# LTC6803-3.net
KiCad netlist of a schematic drawn in Altium Designer
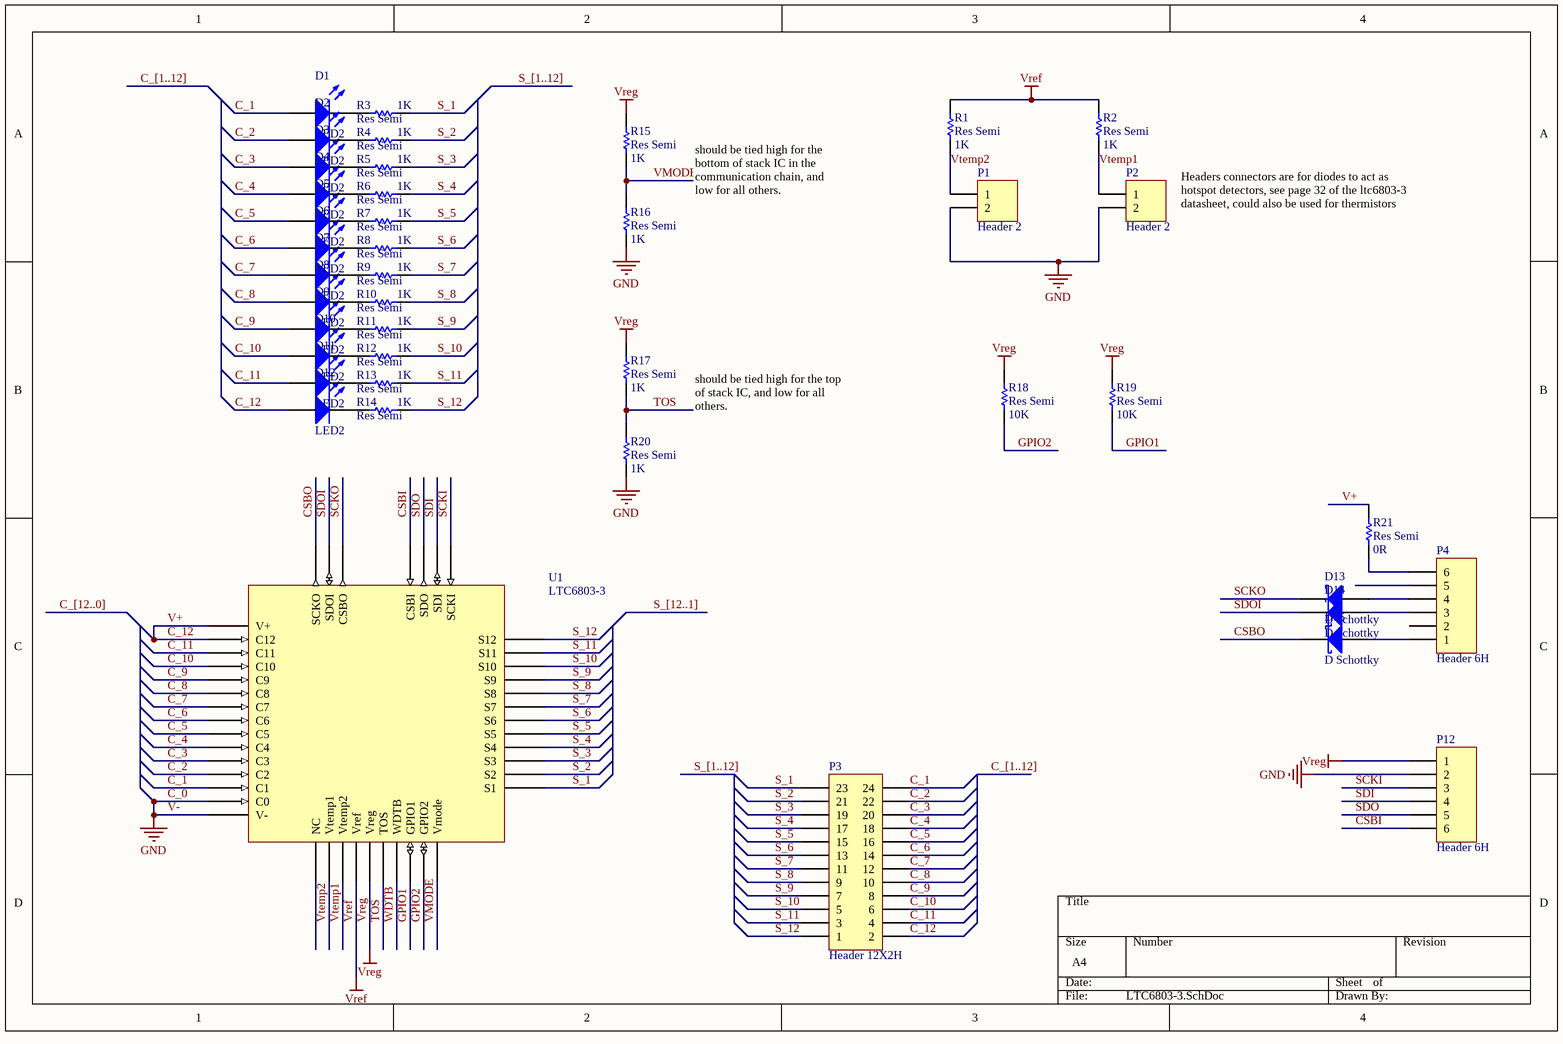
[diagram p0: LTC6803-3.SchDoc]

(export (version "E")
  (design (tool "Eeschema 10.0.6"))
  (components
    (comp (ref "D1")
      (value "LED2")
      (footprint "6-0805_N")
      (description "Typical RED, GREEN, YELLOW, AMBER GaAs LED")
      (fields (field (name "PUBLISHER") "Altium Limited"))
      (libsource (lib "Miscellaneous Devices") (part "LED2"))
    )
    (comp (ref "D2")
      (value "LED2")
      (footprint "6-0805_N")
      (description "Typical RED, GREEN, YELLOW, AMBER GaAs LED")
      (fields (field (name "PUBLISHER") "Altium Limited"))
      (libsource (lib "Miscellaneous Devices") (part "LED2"))
    )
    (comp (ref "D3")
      (value "LED2")
      (footprint "6-0805_N")
      (description "Typical RED, GREEN, YELLOW, AMBER GaAs LED")
      (fields (field (name "PUBLISHER") "Altium Limited"))
      (libsource (lib "Miscellaneous Devices") (part "LED2"))
    )
    (comp (ref "D4")
      (value "LED2")
      (footprint "6-0805_N")
      (description "Typical RED, GREEN, YELLOW, AMBER GaAs LED")
      (fields (field (name "PUBLISHER") "Altium Limited"))
      (libsource (lib "Miscellaneous Devices") (part "LED2"))
    )
    (comp (ref "D5")
      (value "LED2")
      (footprint "6-0805_N")
      (description "Typical RED, GREEN, YELLOW, AMBER GaAs LED")
      (fields (field (name "PUBLISHER") "Altium Limited"))
      (libsource (lib "Miscellaneous Devices") (part "LED2"))
    )
    (comp (ref "D6")
      (value "LED2")
      (footprint "6-0805_N")
      (description "Typical RED, GREEN, YELLOW, AMBER GaAs LED")
      (fields (field (name "PUBLISHER") "Altium Limited"))
      (libsource (lib "Miscellaneous Devices") (part "LED2"))
    )
    (comp (ref "D7")
      (value "LED2")
      (footprint "6-0805_N")
      (description "Typical RED, GREEN, YELLOW, AMBER GaAs LED")
      (fields (field (name "PUBLISHER") "Altium Limited"))
      (libsource (lib "Miscellaneous Devices") (part "LED2"))
    )
    (comp (ref "D8")
      (value "LED2")
      (footprint "6-0805_N")
      (description "Typical RED, GREEN, YELLOW, AMBER GaAs LED")
      (fields (field (name "PUBLISHER") "Altium Limited"))
      (libsource (lib "Miscellaneous Devices") (part "LED2"))
    )
    (comp (ref "D9")
      (value "LED2")
      (footprint "6-0805_N")
      (description "Typical RED, GREEN, YELLOW, AMBER GaAs LED")
      (fields (field (name "PUBLISHER") "Altium Limited"))
      (libsource (lib "Miscellaneous Devices") (part "LED2"))
    )
    (comp (ref "D10")
      (value "LED2")
      (footprint "6-0805_N")
      (description "Typical RED, GREEN, YELLOW, AMBER GaAs LED")
      (fields (field (name "PUBLISHER") "Altium Limited"))
      (libsource (lib "Miscellaneous Devices") (part "LED2"))
    )
    (comp (ref "D11")
      (value "LED2")
      (footprint "6-0805_N")
      (description "Typical RED, GREEN, YELLOW, AMBER GaAs LED")
      (fields (field (name "PUBLISHER") "Altium Limited"))
      (libsource (lib "Miscellaneous Devices") (part "LED2"))
    )
    (comp (ref "D12")
      (value "LED2")
      (footprint "6-0805_N")
      (description "Typical RED, GREEN, YELLOW, AMBER GaAs LED")
      (fields (field (name "PUBLISHER") "Altium Limited"))
      (libsource (lib "Miscellaneous Devices") (part "LED2"))
    )
    (comp (ref "D13")
      (value "D Schottky")
      (footprint "SMB")
      (description "Schottky Diode")
      (fields (field (name "PUBLISHER") "Altium Limited"))
      (libsource (lib "Miscellaneous Devices") (part "D Schottky"))
    )
    (comp (ref "D14")
      (value "D Schottky")
      (footprint "SMB")
      (description "Schottky Diode")
      (fields (field (name "PUBLISHER") "Altium Limited"))
      (libsource (lib "Miscellaneous Devices") (part "D Schottky"))
    )
    (comp (ref "D15")
      (value "D Schottky")
      (footprint "SMB")
      (description "Schottky Diode")
      (fields (field (name "PUBLISHER") "Altium Limited"))
      (libsource (lib "Miscellaneous Devices") (part "D Schottky"))
    )
    (comp (ref "P1")
      (value "Header 2")
      (footprint "HDR1X2")
      (description "Header, 2-Pin")
      (fields (field (name "PUBLISHER") "Altium Limited"))
      (libsource (lib "Miscellaneous Connectors") (part "Header 2"))
    )
    (comp (ref "P2")
      (value "Header 2")
      (footprint "HDR1X2")
      (description "Header, 2-Pin")
      (fields (field (name "PUBLISHER") "Altium Limited"))
      (libsource (lib "Miscellaneous Connectors") (part "Header 2"))
    )
    (comp (ref "P3")
      (value "Header 12X2H")
      (footprint "HDR2X12H")
      (description "Header, 12-Pin, Dual row, Right Angle")
      (fields (field (name "PUBLISHER") "Altium Limited"))
      (libsource (lib "Miscellaneous Connectors") (part "Header 12X2H"))
    )
    (comp (ref "P4")
      (value "Header 6H")
      (footprint "HDR1X6H")
      (description "Header, 6-Pin, Right Angle")
      (fields (field (name "PUBLISHER") "Altium Limited"))
      (libsource (lib "") (part "Header 6H_1"))
    )
    (comp (ref "P12")
      (value "Header 6H")
      (footprint "HDR1X6H")
      (description "Header, 6-Pin, Right Angle")
      (fields (field (name "PUBLISHER") "Altium Limited"))
      (libsource (lib "Miscellaneous Connectors") (part "Header 6H"))
    )
    (comp (ref "R1")
      (value "Res Semi")
      (footprint "6-0805_L")
      (description "Semiconductor Resistor")
      (fields (field (name "ALTIUM_VALUE") "1K") (field (name "PUBLISHER") "Altium Limited"))
      (libsource (lib "Miscellaneous Devices") (part "Res Semi"))
    )
    (comp (ref "R2")
      (value "Res Semi")
      (footprint "6-0805_L")
      (description "Semiconductor Resistor")
      (fields (field (name "ALTIUM_VALUE") "1K") (field (name "PUBLISHER") "Altium Limited"))
      (libsource (lib "Miscellaneous Devices") (part "Res Semi"))
    )
    (comp (ref "R3")
      (value "Res Semi")
      (footprint "6-0805_L")
      (description "Semiconductor Resistor")
      (fields (field (name "ALTIUM_VALUE") "1K") (field (name "PUBLISHER") "Altium Limited"))
      (libsource (lib "Miscellaneous Devices") (part "Res Semi"))
    )
    (comp (ref "R4")
      (value "Res Semi")
      (footprint "6-0805_L")
      (description "Semiconductor Resistor")
      (fields (field (name "ALTIUM_VALUE") "1K") (field (name "PUBLISHER") "Altium Limited"))
      (libsource (lib "Miscellaneous Devices") (part "Res Semi"))
    )
    (comp (ref "R5")
      (value "Res Semi")
      (footprint "6-0805_L")
      (description "Semiconductor Resistor")
      (fields (field (name "ALTIUM_VALUE") "1K") (field (name "PUBLISHER") "Altium Limited"))
      (libsource (lib "Miscellaneous Devices") (part "Res Semi"))
    )
    (comp (ref "R6")
      (value "Res Semi")
      (footprint "6-0805_L")
      (description "Semiconductor Resistor")
      (fields (field (name "ALTIUM_VALUE") "1K") (field (name "PUBLISHER") "Altium Limited"))
      (libsource (lib "Miscellaneous Devices") (part "Res Semi"))
    )
    (comp (ref "R7")
      (value "Res Semi")
      (footprint "6-0805_L")
      (description "Semiconductor Resistor")
      (fields (field (name "ALTIUM_VALUE") "1K") (field (name "PUBLISHER") "Altium Limited"))
      (libsource (lib "Miscellaneous Devices") (part "Res Semi"))
    )
    (comp (ref "R8")
      (value "Res Semi")
      (footprint "6-0805_L")
      (description "Semiconductor Resistor")
      (fields (field (name "ALTIUM_VALUE") "1K") (field (name "PUBLISHER") "Altium Limited"))
      (libsource (lib "Miscellaneous Devices") (part "Res Semi"))
    )
    (comp (ref "R9")
      (value "Res Semi")
      (footprint "6-0805_L")
      (description "Semiconductor Resistor")
      (fields (field (name "ALTIUM_VALUE") "1K") (field (name "PUBLISHER") "Altium Limited"))
      (libsource (lib "Miscellaneous Devices") (part "Res Semi"))
    )
    (comp (ref "R10")
      (value "Res Semi")
      (footprint "6-0805_L")
      (description "Semiconductor Resistor")
      (fields (field (name "ALTIUM_VALUE") "1K") (field (name "PUBLISHER") "Altium Limited"))
      (libsource (lib "Miscellaneous Devices") (part "Res Semi"))
    )
    (comp (ref "R11")
      (value "Res Semi")
      (footprint "6-0805_L")
      (description "Semiconductor Resistor")
      (fields (field (name "ALTIUM_VALUE") "1K") (field (name "PUBLISHER") "Altium Limited"))
      (libsource (lib "Miscellaneous Devices") (part "Res Semi"))
    )
    (comp (ref "R12")
      (value "Res Semi")
      (footprint "6-0805_L")
      (description "Semiconductor Resistor")
      (fields (field (name "ALTIUM_VALUE") "1K") (field (name "PUBLISHER") "Altium Limited"))
      (libsource (lib "Miscellaneous Devices") (part "Res Semi"))
    )
    (comp (ref "R13")
      (value "Res Semi")
      (footprint "6-0805_L")
      (description "Semiconductor Resistor")
      (fields (field (name "ALTIUM_VALUE") "1K") (field (name "PUBLISHER") "Altium Limited"))
      (libsource (lib "Miscellaneous Devices") (part "Res Semi"))
    )
    (comp (ref "R14")
      (value "Res Semi")
      (footprint "6-0805_L")
      (description "Semiconductor Resistor")
      (fields (field (name "ALTIUM_VALUE") "1K") (field (name "PUBLISHER") "Altium Limited"))
      (libsource (lib "Miscellaneous Devices") (part "Res Semi"))
    )
    (comp (ref "R15")
      (value "Res Semi")
      (footprint "6-0805_L")
      (description "Semiconductor Resistor")
      (fields (field (name "ALTIUM_VALUE") "1K") (field (name "PUBLISHER") "Altium Limited"))
      (libsource (lib "Miscellaneous Devices") (part "Res Semi"))
    )
    (comp (ref "R16")
      (value "Res Semi")
      (footprint "6-0805_L")
      (description "Semiconductor Resistor")
      (fields (field (name "ALTIUM_VALUE") "1K") (field (name "PUBLISHER") "Altium Limited"))
      (libsource (lib "Miscellaneous Devices") (part "Res Semi"))
    )
    (comp (ref "R17")
      (value "Res Semi")
      (footprint "6-0805_L")
      (description "Semiconductor Resistor")
      (fields (field (name "ALTIUM_VALUE") "1K") (field (name "PUBLISHER") "Altium Limited"))
      (libsource (lib "Miscellaneous Devices") (part "Res Semi"))
    )
    (comp (ref "R18")
      (value "Res Semi")
      (footprint "6-0805_L")
      (description "Semiconductor Resistor")
      (fields (field (name "ALTIUM_VALUE") "10K") (field (name "PUBLISHER") "Altium Limited"))
      (libsource (lib "Miscellaneous Devices") (part "Res Semi"))
    )
    (comp (ref "R19")
      (value "Res Semi")
      (footprint "6-0805_L")
      (description "Semiconductor Resistor")
      (fields (field (name "ALTIUM_VALUE") "10K") (field (name "PUBLISHER") "Altium Limited"))
      (libsource (lib "Miscellaneous Devices") (part "Res Semi"))
    )
    (comp (ref "R20")
      (value "Res Semi")
      (footprint "6-0805_L")
      (description "Semiconductor Resistor")
      (fields (field (name "ALTIUM_VALUE") "1K") (field (name "PUBLISHER") "Altium Limited"))
      (libsource (lib "Miscellaneous Devices") (part "Res Semi"))
    )
    (comp (ref "R21")
      (value "Res Semi")
      (footprint "6-0805_L")
      (description "Semiconductor Resistor")
      (fields (field (name "ALTIUM_VALUE") "0R") (field (name "PUBLISHER") "Altium Limited"))
      (libsource (lib "Miscellaneous Devices") (part "Res Semi"))
    )
    (comp (ref "U1") (value "LTC6803-3") (footprint "SOP44") (libsource (lib "BMS") (part "LTC6803-3")))
  )
  (nets
    (net (code "1") (name "/CSBI") (class "Default")
      (node (ref "P12") (pin "6") (pinfunction "6_6") (pintype "passive"))
      (node (ref "U1") (pin "44") (pinfunction "CSBI_44") (pintype "input"))
    )
    (net (code "2") (name "/CSBO") (class "Default")
      (node (ref "D15") (pin "2") (pinfunction "K_2") (pintype "passive"))
      (node (ref "U1") (pin "3") (pinfunction "SCKO_3") (pintype "output"))
    )
    (net (code "3") (name "/C_1") (class "Default")
      (node (ref "D1") (pin "1") (pinfunction "A_1") (pintype "passive"))
      (node (ref "P3") (pin "24") (pinfunction "24_24") (pintype "passive"))
      (node (ref "U1") (pin "27") (pinfunction "C1_27") (pintype "input"))
    )
    (net (code "4") (name "/C_2") (class "Default")
      (node (ref "D2") (pin "1") (pinfunction "A_1") (pintype "passive"))
      (node (ref "P3") (pin "22") (pinfunction "22_22") (pintype "passive"))
      (node (ref "U1") (pin "25") (pinfunction "C2_25") (pintype "input"))
    )
    (net (code "5") (name "/C_3") (class "Default")
      (node (ref "D3") (pin "1") (pinfunction "A_1") (pintype "passive"))
      (node (ref "P3") (pin "20") (pinfunction "20_20") (pintype "passive"))
      (node (ref "U1") (pin "23") (pinfunction "C3_23") (pintype "input"))
    )
    (net (code "6") (name "/C_4") (class "Default")
      (node (ref "D4") (pin "1") (pinfunction "A_1") (pintype "passive"))
      (node (ref "P3") (pin "18") (pinfunction "18_18") (pintype "passive"))
      (node (ref "U1") (pin "21") (pinfunction "C4_21") (pintype "input"))
    )
    (net (code "7") (name "/C_5") (class "Default")
      (node (ref "D5") (pin "1") (pinfunction "A_1") (pintype "passive"))
      (node (ref "P3") (pin "16") (pinfunction "16_16") (pintype "passive"))
      (node (ref "U1") (pin "19") (pinfunction "C5_19") (pintype "input"))
    )
    (net (code "8") (name "/C_6") (class "Default")
      (node (ref "D6") (pin "1") (pinfunction "A_1") (pintype "passive"))
      (node (ref "P3") (pin "14") (pinfunction "14_14") (pintype "passive"))
      (node (ref "U1") (pin "17") (pinfunction "C6_17") (pintype "input"))
    )
    (net (code "9") (name "/C_7") (class "Default")
      (node (ref "D7") (pin "1") (pinfunction "A_1") (pintype "passive"))
      (node (ref "P3") (pin "12") (pinfunction "12_12") (pintype "passive"))
      (node (ref "U1") (pin "15") (pinfunction "C7_15") (pintype "input"))
    )
    (net (code "10") (name "/C_8") (class "Default")
      (node (ref "D8") (pin "1") (pinfunction "A_1") (pintype "passive"))
      (node (ref "P3") (pin "10") (pinfunction "10_10") (pintype "passive"))
      (node (ref "U1") (pin "13") (pinfunction "C8_13") (pintype "input"))
    )
    (net (code "11") (name "/C_9") (class "Default")
      (node (ref "D9") (pin "1") (pinfunction "A_1") (pintype "passive"))
      (node (ref "P3") (pin "8") (pinfunction "8_8") (pintype "passive"))
      (node (ref "U1") (pin "11") (pinfunction "C9_11") (pintype "input"))
    )
    (net (code "12") (name "/C_10") (class "Default")
      (node (ref "D10") (pin "1") (pinfunction "A_1") (pintype "passive"))
      (node (ref "P3") (pin "6") (pinfunction "6_6") (pintype "passive"))
      (node (ref "U1") (pin "9") (pinfunction "C10_9") (pintype "input"))
    )
    (net (code "13") (name "/C_11") (class "Default")
      (node (ref "D11") (pin "1") (pinfunction "A_1") (pintype "passive"))
      (node (ref "P3") (pin "4") (pinfunction "4_4") (pintype "passive"))
      (node (ref "U1") (pin "7") (pinfunction "C11_7") (pintype "input"))
    )
    (net (code "14") (name "/C_12") (class "Default")
      (node (ref "D12") (pin "1") (pinfunction "A_1") (pintype "passive"))
      (node (ref "P3") (pin "2") (pinfunction "2_2") (pintype "passive"))
      (node (ref "R21") (pin "2") (pinfunction "2_2") (pintype "passive"))
      (node (ref "U1") (pin "4") (pinfunction "V+_4") (pintype "power_in"))
      (node (ref "U1") (pin "5") (pinfunction "C12_5") (pintype "input"))
    )
    (net (code "17") (name "/GPIO1") (class "Default")
      (node (ref "R19") (pin "1") (pinfunction "1_1") (pintype "passive"))
      (node (ref "U1") (pin "38") (pinfunction "GPIO1_38") (pintype "bidirectional"))
    )
    (net (code "18") (name "/GPIO2") (class "Default")
      (node (ref "R18") (pin "1") (pinfunction "1_1") (pintype "passive"))
      (node (ref "U1") (pin "39") (pinfunction "GPIO2_39") (pintype "bidirectional"))
    )
    (net (code "19") (name "/SCKI") (class "Default")
      (node (ref "P12") (pin "3") (pinfunction "3_3") (pintype "passive"))
      (node (ref "U1") (pin "41") (pinfunction "SCKI_41") (pintype "input"))
    )
    (net (code "20") (name "/SCKO") (class "Default")
      (node (ref "D13") (pin "2") (pinfunction "K_2") (pintype "passive"))
      (node (ref "U1") (pin "1") (pinfunction "CSBO_1") (pintype "output"))
    )
    (net (code "21") (name "/SDI") (class "Default")
      (node (ref "P12") (pin "4") (pinfunction "4_4") (pintype "passive"))
      (node (ref "U1") (pin "42") (pinfunction "SDI_42") (pintype "bidirectional"))
    )
    (net (code "22") (name "/SDO") (class "Default")
      (node (ref "P12") (pin "5") (pinfunction "5_5") (pintype "passive"))
      (node (ref "U1") (pin "43") (pinfunction "SDO_43") (pintype "output"))
    )
    (net (code "23") (name "/SDOI") (class "Default")
      (node (ref "D14") (pin "2") (pinfunction "K_2") (pintype "passive"))
      (node (ref "U1") (pin "2") (pinfunction "SDOI_2") (pintype "bidirectional"))
    )
    (net (code "24") (name "/S_1") (class "Default")
      (node (ref "P3") (pin "23") (pinfunction "23_23") (pintype "passive"))
      (node (ref "R3") (pin "2") (pinfunction "2_2") (pintype "passive"))
      (node (ref "U1") (pin "28") (pinfunction "S1_28") (pintype "passive"))
    )
    (net (code "25") (name "/S_2") (class "Default")
      (node (ref "P3") (pin "21") (pinfunction "21_21") (pintype "passive"))
      (node (ref "R4") (pin "2") (pinfunction "2_2") (pintype "passive"))
      (node (ref "U1") (pin "26") (pinfunction "S2_26") (pintype "passive"))
    )
    (net (code "26") (name "/S_3") (class "Default")
      (node (ref "P3") (pin "19") (pinfunction "19_19") (pintype "passive"))
      (node (ref "R5") (pin "2") (pinfunction "2_2") (pintype "passive"))
      (node (ref "U1") (pin "24") (pinfunction "S3_24") (pintype "passive"))
    )
    (net (code "27") (name "/S_4") (class "Default")
      (node (ref "P3") (pin "17") (pinfunction "17_17") (pintype "passive"))
      (node (ref "R6") (pin "2") (pinfunction "2_2") (pintype "passive"))
      (node (ref "U1") (pin "22") (pinfunction "S4_22") (pintype "passive"))
    )
    (net (code "28") (name "/S_5") (class "Default")
      (node (ref "P3") (pin "15") (pinfunction "15_15") (pintype "passive"))
      (node (ref "R7") (pin "2") (pinfunction "2_2") (pintype "passive"))
      (node (ref "U1") (pin "20") (pinfunction "S5_20") (pintype "passive"))
    )
    (net (code "29") (name "/S_6") (class "Default")
      (node (ref "P3") (pin "13") (pinfunction "13_13") (pintype "passive"))
      (node (ref "R8") (pin "2") (pinfunction "2_2") (pintype "passive"))
      (node (ref "U1") (pin "18") (pinfunction "S6_18") (pintype "passive"))
    )
    (net (code "30") (name "/S_7") (class "Default")
      (node (ref "P3") (pin "11") (pinfunction "11_11") (pintype "passive"))
      (node (ref "R9") (pin "2") (pinfunction "2_2") (pintype "passive"))
      (node (ref "U1") (pin "16") (pinfunction "S7_16") (pintype "passive"))
    )
    (net (code "31") (name "/S_8") (class "Default")
      (node (ref "P3") (pin "9") (pinfunction "9_9") (pintype "passive"))
      (node (ref "R10") (pin "2") (pinfunction "2_2") (pintype "passive"))
      (node (ref "U1") (pin "14") (pinfunction "S8_14") (pintype "passive"))
    )
    (net (code "32") (name "/S_9") (class "Default")
      (node (ref "P3") (pin "7") (pinfunction "7_7") (pintype "passive"))
      (node (ref "R11") (pin "2") (pinfunction "2_2") (pintype "passive"))
      (node (ref "U1") (pin "12") (pinfunction "S9_12") (pintype "passive"))
    )
    (net (code "33") (name "/S_10") (class "Default")
      (node (ref "P3") (pin "5") (pinfunction "5_5") (pintype "passive"))
      (node (ref "R12") (pin "2") (pinfunction "2_2") (pintype "passive"))
      (node (ref "U1") (pin "10") (pinfunction "S10_10") (pintype "passive"))
    )
    (net (code "34") (name "/S_11") (class "Default")
      (node (ref "P3") (pin "3") (pinfunction "3_3") (pintype "passive"))
      (node (ref "R13") (pin "2") (pinfunction "2_2") (pintype "passive"))
      (node (ref "U1") (pin "8") (pinfunction "S11_8") (pintype "passive"))
    )
    (net (code "35") (name "/S_12") (class "Default")
      (node (ref "P3") (pin "1") (pinfunction "1_1") (pintype "passive"))
      (node (ref "R14") (pin "2") (pinfunction "2_2") (pintype "passive"))
      (node (ref "U1") (pin "6") (pinfunction "S12_6") (pintype "passive"))
    )
    (net (code "38") (name "/TOS") (class "Default")
      (node (ref "R17") (pin "1") (pinfunction "1_1") (pintype "passive"))
      (node (ref "R20") (pin "2") (pinfunction "2_2") (pintype "passive"))
      (node (ref "U1") (pin "36") (pinfunction "TOS_36") (pintype "passive"))
    )
    (net (code "39") (name "/VMODE") (class "Default")
      (node (ref "R15") (pin "1") (pinfunction "1_1") (pintype "passive"))
      (node (ref "R16") (pin "2") (pinfunction "2_2") (pintype "passive"))
      (node (ref "U1") (pin "40") (pinfunction "Vmode_40") (pintype "passive"))
    )
    (net (code "40") (name "/Vtemp1") (class "Default")
      (node (ref "P2") (pin "1") (pinfunction "1_1") (pintype "passive"))
      (node (ref "R2") (pin "1") (pinfunction "1_1") (pintype "passive"))
      (node (ref "U1") (pin "33") (pinfunction "Vtemp2_33") (pintype "passive"))
    )
    (net (code "41") (name "/Vtemp2") (class "Default")
      (node (ref "P1") (pin "1") (pinfunction "1_1") (pintype "passive"))
      (node (ref "R1") (pin "1") (pinfunction "1_1") (pintype "passive"))
      (node (ref "U1") (pin "32") (pinfunction "Vtemp1_32") (pintype "passive"))
    )
    (net (code "42") (name "/WDTB") (class "Default")
      (node (ref "U1") (pin "37") (pinfunction "WDTB_37") (pintype "passive"))
    )
    (net (code "43") (name "GND") (class "Default")
      (node (ref "P1") (pin "2") (pinfunction "2_2") (pintype "passive"))
      (node (ref "P12") (pin "2") (pinfunction "2_2") (pintype "passive"))
      (node (ref "P2") (pin "2") (pinfunction "2_2") (pintype "passive"))
      (node (ref "R16") (pin "1") (pinfunction "1_1") (pintype "passive"))
      (node (ref "R20") (pin "1") (pinfunction "1_1") (pintype "passive"))
      (node (ref "U1") (pin "29") (pinfunction "C0_29") (pintype "input"))
      (node (ref "U1") (pin "30") (pinfunction "V-_30") (pintype "power_in"))
    )
    (net (code "44") (name "Net-(D1-K)") (class "Default")
      (node (ref "D1") (pin "2") (pinfunction "K_2") (pintype "passive"))
      (node (ref "R3") (pin "1") (pinfunction "1_1") (pintype "passive"))
    )
    (net (code "45") (name "Net-(D2-K)") (class "Default")
      (node (ref "D2") (pin "2") (pinfunction "K_2") (pintype "passive"))
      (node (ref "R4") (pin "1") (pinfunction "1_1") (pintype "passive"))
    )
    (net (code "46") (name "Net-(D3-K)") (class "Default")
      (node (ref "D3") (pin "2") (pinfunction "K_2") (pintype "passive"))
      (node (ref "R5") (pin "1") (pinfunction "1_1") (pintype "passive"))
    )
    (net (code "47") (name "Net-(D4-K)") (class "Default")
      (node (ref "D4") (pin "2") (pinfunction "K_2") (pintype "passive"))
      (node (ref "R6") (pin "1") (pinfunction "1_1") (pintype "passive"))
    )
    (net (code "48") (name "Net-(D5-K)") (class "Default")
      (node (ref "D5") (pin "2") (pinfunction "K_2") (pintype "passive"))
      (node (ref "R7") (pin "1") (pinfunction "1_1") (pintype "passive"))
    )
    (net (code "49") (name "Net-(D6-K)") (class "Default")
      (node (ref "D6") (pin "2") (pinfunction "K_2") (pintype "passive"))
      (node (ref "R8") (pin "1") (pinfunction "1_1") (pintype "passive"))
    )
    (net (code "50") (name "Net-(D7-K)") (class "Default")
      (node (ref "D7") (pin "2") (pinfunction "K_2") (pintype "passive"))
      (node (ref "R9") (pin "1") (pinfunction "1_1") (pintype "passive"))
    )
    (net (code "51") (name "Net-(D8-K)") (class "Default")
      (node (ref "D8") (pin "2") (pinfunction "K_2") (pintype "passive"))
      (node (ref "R10") (pin "1") (pinfunction "1_1") (pintype "passive"))
    )
    (net (code "52") (name "Net-(D9-K)") (class "Default")
      (node (ref "D9") (pin "2") (pinfunction "K_2") (pintype "passive"))
      (node (ref "R11") (pin "1") (pinfunction "1_1") (pintype "passive"))
    )
    (net (code "53") (name "Net-(D10-K)") (class "Default")
      (node (ref "D10") (pin "2") (pinfunction "K_2") (pintype "passive"))
      (node (ref "R12") (pin "1") (pinfunction "1_1") (pintype "passive"))
    )
    (net (code "54") (name "Net-(D11-K)") (class "Default")
      (node (ref "D11") (pin "2") (pinfunction "K_2") (pintype "passive"))
      (node (ref "R13") (pin "1") (pinfunction "1_1") (pintype "passive"))
    )
    (net (code "55") (name "Net-(D12-K)") (class "Default")
      (node (ref "D12") (pin "2") (pinfunction "K_2") (pintype "passive"))
      (node (ref "R14") (pin "1") (pinfunction "1_1") (pintype "passive"))
    )
    (net (code "56") (name "Net-(D13-A)") (class "Default")
      (node (ref "D13") (pin "1") (pinfunction "A_1") (pintype "passive"))
      (node (ref "P4") (pin "4") (pinfunction "4_4") (pintype "passive"))
    )
    (net (code "57") (name "Net-(D14-A)") (class "Default")
      (node (ref "D14") (pin "1") (pinfunction "A_1") (pintype "passive"))
      (node (ref "P4") (pin "3") (pinfunction "3_3") (pintype "passive"))
    )
    (net (code "58") (name "Net-(D15-A)") (class "Default")
      (node (ref "D15") (pin "1") (pinfunction "A_1") (pintype "passive"))
      (node (ref "P4") (pin "1") (pinfunction "1_1") (pintype "passive"))
    )
    (net (code "59") (name "Net-(P4-Pad6)") (class "Default")
      (node (ref "P4") (pin "6") (pinfunction "6_6") (pintype "passive"))
      (node (ref "R21") (pin "1") (pinfunction "1_1") (pintype "passive"))
    )
    (net (code "60") (name "Vref") (class "Default")
      (node (ref "R1") (pin "2") (pinfunction "2_2") (pintype "passive"))
      (node (ref "R2") (pin "2") (pinfunction "2_2") (pintype "passive"))
      (node (ref "U1") (pin "34") (pinfunction "Vref_34") (pintype "passive"))
    )
    (net (code "61") (name "Vreg") (class "Default")
      (node (ref "P12") (pin "1") (pinfunction "1_1") (pintype "passive"))
      (node (ref "R15") (pin "2") (pinfunction "2_2") (pintype "passive"))
      (node (ref "R17") (pin "2") (pinfunction "2_2") (pintype "passive"))
      (node (ref "R18") (pin "2") (pinfunction "2_2") (pintype "passive"))
      (node (ref "R19") (pin "2") (pinfunction "2_2") (pintype "passive"))
      (node (ref "U1") (pin "35") (pinfunction "Vreg_35") (pintype "passive"))
    )
    (net (code "62") (name "unconnected-(P4-Pad2)") (class "Default")
      (node (ref "P4") (pin "2") (pinfunction "2_2") (pintype "passive"))
    )
    (net (code "63") (name "unconnected-(P4-Pad5)") (class "Default")
      (node (ref "P4") (pin "5") (pinfunction "5_5") (pintype "passive"))
    )
    (net (code "64") (name "unconnected-(U1-NC-Pad31)") (class "Default")
      (node (ref "U1") (pin "31") (pinfunction "NC_31") (pintype "passive"))
    )
  )
)
